# VSupply3.net
KiCad netlist of a schematic drawn in Altium Designer
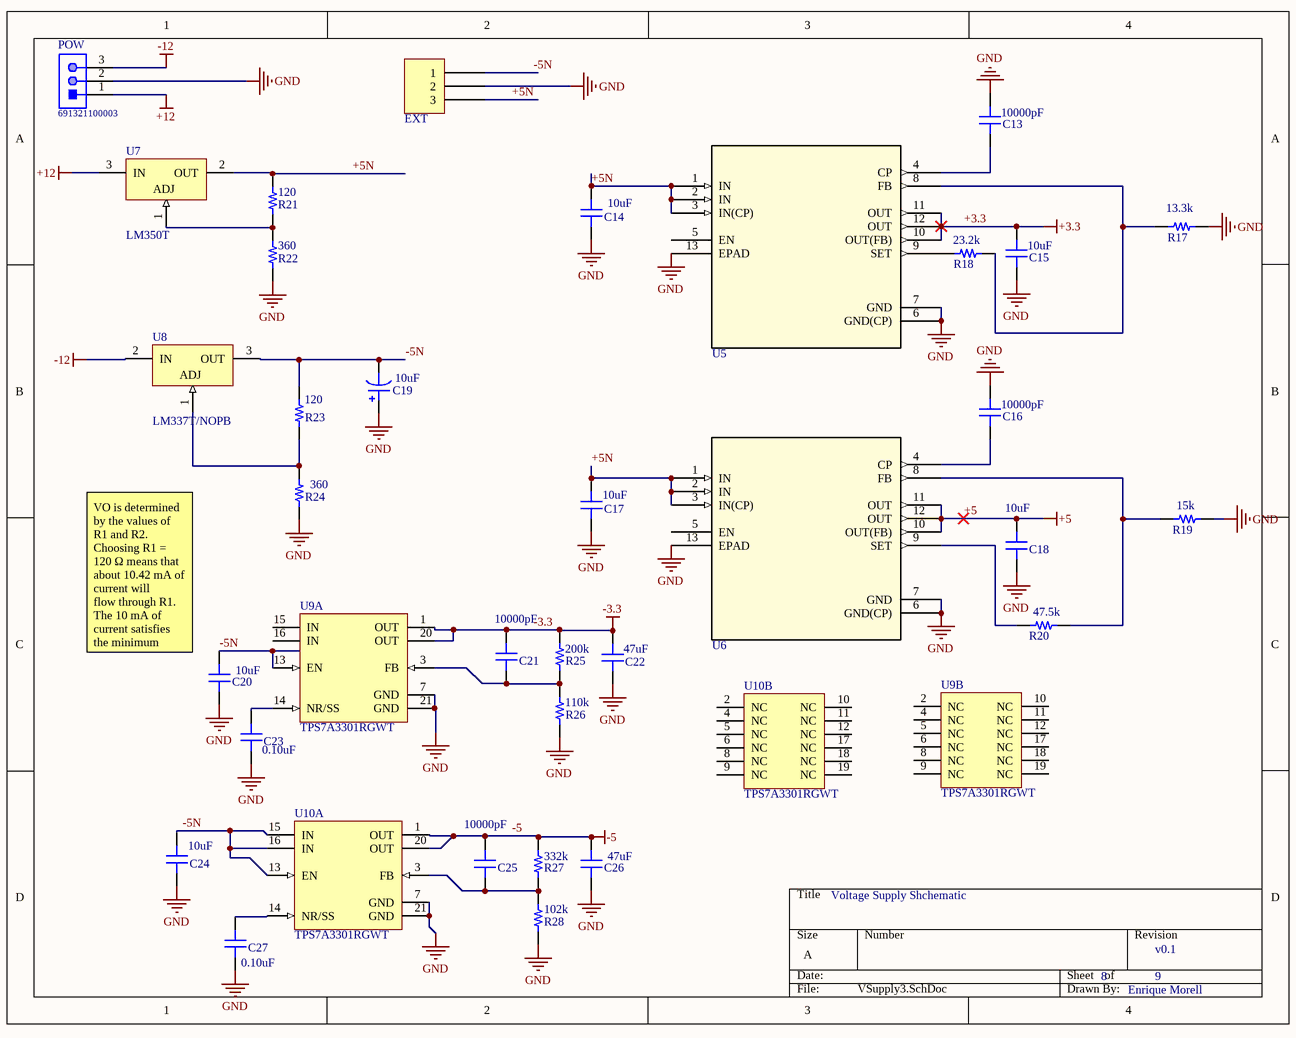
[diagram p0: VSupply3.SchDoc]

(export (version "E")
  (design (tool "Eeschema 10.0.6"))
  (components
    (comp (ref "C13")
      (value "10000pF")
      (footprint "CAP 0402/1005")
      (description "CAP CER 10000PF 16V X7R 0402")
      (fields (field (name "PART NUMBER") "C0402C103J4RACTU") (field (name "MANUFACTURER") "Kemet"))
      (libsource (lib "Celestial Library Database") (part "Capacitor"))
    )
    (comp (ref "C14")
      (value "10uF")
      (footprint "CAP 1210/3225 - 2.8MM")
      (description "CAP CER 10UF 25V X7R 1210")
      (fields
        (field (name "PART NUMBER") "CL32B106KAJNNNE")
        (field (name "MANUFACTURER") "Samsung Electro-Mechanics America, Inc.")
      )
      (libsource (lib "Celestial Library Database") (part "Capacitor"))
    )
    (comp (ref "C15")
      (value "10uF")
      (footprint "CAP 1210/3225 - 2.8MM")
      (description "CAP CER 10UF 25V X7R 1210")
      (fields
        (field (name "PART NUMBER") "CL32B106KAJNNNE")
        (field (name "MANUFACTURER") "Samsung Electro-Mechanics America, Inc.")
      )
      (libsource (lib "Celestial Library Database") (part "Capacitor"))
    )
    (comp (ref "C16")
      (value "10000pF")
      (footprint "CAP 0402/1005")
      (description "CAP CER 10000PF 16V X7R 0402")
      (fields (field (name "PART NUMBER") "C0402C103J4RACTU") (field (name "MANUFACTURER") "Kemet"))
      (libsource (lib "Celestial Library Database") (part "Capacitor"))
    )
    (comp (ref "C17")
      (value "10uF")
      (footprint "CAP 1210/3225 - 2.8MM")
      (description "CAP CER 10UF 25V X7R 1210")
      (fields
        (field (name "PART NUMBER") "CL32B106KAJNNNE")
        (field (name "MANUFACTURER") "Samsung Electro-Mechanics America, Inc.")
      )
      (libsource (lib "Celestial Library Database") (part "Capacitor"))
    )
    (comp (ref "C18")
      (value "10uF")
      (footprint "CAP 1210/3225 - 2.8MM")
      (description "CAP CER 10UF 25V X7R 1210")
      (fields
        (field (name "PART NUMBER") "CL32B106KAJNNNE")
        (field (name "MANUFACTURER") "Samsung Electro-Mechanics America, Inc.")
      )
      (libsource (lib "Celestial Library Database") (part "Capacitor"))
    )
    (comp (ref "C19")
      (value "10uF")
      (footprint "CAP POL 2917/7343")
      (description "CAP TANT 10UF 35V 20% 2917")
      (fields (field (name "PART NUMBER") "293D106X0035D2TE3") (field (name "MANUFACTURER") "Vishay Sprague"))
      (libsource (lib "Celestial Library Database") (part "Polarised Capacitor"))
    )
    (comp (ref "C20")
      (value "10uF")
      (footprint "CAP 1210/3225 - 2.8MM")
      (description "CAP CER 10UF 25V X7R 1210")
      (fields
        (field (name "PART NUMBER") "CL32B106KAJNNNE")
        (field (name "MANUFACTURER") "Samsung Electro-Mechanics America, Inc.")
      )
      (libsource (lib "Celestial Library Database") (part "Capacitor"))
    )
    (comp (ref "C21")
      (value "10000pF")
      (footprint "CAP 0402/1005")
      (description "CAP CER 10000PF 16V X7R 0402")
      (fields (field (name "PART NUMBER") "C0402C103J4RACTU") (field (name "MANUFACTURER") "Kemet"))
      (libsource (lib "Celestial Library Database") (part "Capacitor"))
    )
    (comp (ref "C22")
      (value "47uF")
      (footprint "CAP 1206/3216")
      (description "CAP CER 47UF 25V X5R 1206")
      (fields
        (field (name "PART NUMBER") "C3216X5R1E476M160AC")
        (field (name "MANUFACTURER") "TDK Corporation")
      )
      (libsource (lib "Celestial Library Database") (part "Capacitor"))
    )
    (comp (ref "C23")
      (value "0.10uF")
      (footprint "CAP 0402/1005")
      (description "CAP CER 0.1UF 16V X7R 0402")
      (fields
        (field (name "PART NUMBER") "GRM155R71C104JA88D")
        (field (name "MANUFACTURER") "Murata Electronics North America")
      )
      (libsource (lib "Celestial Library Database") (part "Capacitor"))
    )
    (comp (ref "C24")
      (value "10uF")
      (footprint "CAP 1210/3225 - 2.8MM")
      (description "CAP CER 10UF 25V X7R 1210")
      (fields
        (field (name "PART NUMBER") "CL32B106KAJNNNE")
        (field (name "MANUFACTURER") "Samsung Electro-Mechanics America, Inc.")
      )
      (libsource (lib "Celestial Library Database") (part "Capacitor"))
    )
    (comp (ref "C25")
      (value "10000pF")
      (footprint "CAP 0402/1005")
      (description "CAP CER 10000PF 16V X7R 0402")
      (fields (field (name "PART NUMBER") "C0402C103J4RACTU") (field (name "MANUFACTURER") "Kemet"))
      (libsource (lib "Celestial Library Database") (part "Capacitor"))
    )
    (comp (ref "C26")
      (value "47uF")
      (footprint "CAP 1206/3216")
      (description "CAP CER 47UF 25V X5R 1206")
      (fields
        (field (name "PART NUMBER") "C3216X5R1E476M160AC")
        (field (name "MANUFACTURER") "TDK Corporation")
      )
      (libsource (lib "Celestial Library Database") (part "Capacitor"))
    )
    (comp (ref "C27")
      (value "0.10uF")
      (footprint "CAP 0402/1005")
      (description "CAP CER 0.1UF 16V X7R 0402")
      (fields
        (field (name "PART NUMBER") "GRM155R71C104JA88D")
        (field (name "MANUFACTURER") "Murata Electronics North America")
      )
      (libsource (lib "Celestial Library Database") (part "Capacitor"))
    )
    (comp (ref "EXT")
      (value "0022272031")
      (footprint "MOLEX KK 0022272031")
      (description "CONN HEADER 3POS .100 VERT TIN")
      (fields (field (name "MANUFACTURER") "Molex, LLC"))
      (libsource (lib "Celestial Library Database") (part "3 Pin"))
    )
    (comp (ref "POW")
      (value "691321100003")
      (footprint "691321100003")
      (description "Serie 3211 - 3.50mm Vertical PCB Header WR-TBL, 3 pin")
      (fields (field (name "MANUFACTURER") "Wurth Elektronik") (field (name "PUBLISHER") "WurthElektronik"))
      (libsource (lib "Altium Content Vault") (part "WE-CN-1P-M-R3"))
    )
    (comp (ref "R17")
      (value "13.3k")
      (footprint "RES 0402/1005")
      (description "RES SMD 13.3K OHM 1% 1/10W 0402")
      (fields
        (field (name "PART NUMBER") "ERJ-2RKF1332X")
        (field (name "MANUFACTURER") "Panasonic Electronic Components")
      )
      (libsource (lib "Celestial Library Database") (part "Resistor"))
    )
    (comp (ref "R18")
      (value "23.2k")
      (footprint "RES 0402/1005")
      (description "RES SMD 23.2K OHM 1% 1/10W 0402")
      (fields
        (field (name "PART NUMBER") "ERJ-2RKF2322X")
        (field (name "MANUFACTURER") "Panasonic Electronic Components")
      )
      (libsource (lib "Celestial Library Database") (part "Resistor"))
    )
    (comp (ref "R19")
      (value "15k")
      (footprint "RES 0402/1005")
      (description "RES SMD 15K OHM 1% 1/10W 0402")
      (fields
        (field (name "PART NUMBER") "ERJ-2RKF1502X")
        (field (name "MANUFACTURER") "Panasonic Electronic Components")
      )
      (libsource (lib "Celestial Library Database") (part "Resistor"))
    )
    (comp (ref "R20")
      (value "47.5k")
      (footprint "RES 0402/1005")
      (description "RES SMD 47.5K OHM 1% 1/10W 0402")
      (fields
        (field (name "PART NUMBER") "ERJ-2RKF4752X")
        (field (name "MANUFACTURER") "Panasonic Electronic Components")
      )
      (libsource (lib "Celestial Library Database") (part "Resistor"))
    )
    (comp (ref "R21")
      (value "120")
      (footprint "RES 0402/1005")
      (description "RES SMD 120 OHM 1% 1/10W 0402")
      (fields
        (field (name "PART NUMBER") "ERJ-2RKF1200X")
        (field (name "MANUFACTURER") "Panasonic Electronic Components")
      )
      (libsource (lib "Celestial Library Database") (part "Resistor"))
    )
    (comp (ref "R22")
      (value "360")
      (footprint "RES 0402/1005")
      (description "RES SMD 360 OHM 1% 1/10W 0402")
      (fields
        (field (name "PART NUMBER") "ERJ-2RKF3600X")
        (field (name "MANUFACTURER") "Panasonic Electronic Components")
      )
      (libsource (lib "Celestial Library Database") (part "Resistor"))
    )
    (comp (ref "R23")
      (value "120")
      (footprint "RES 0402/1005")
      (description "RES SMD 120 OHM 1% 1/10W 0402")
      (fields
        (field (name "PART NUMBER") "ERJ-2RKF1200X")
        (field (name "MANUFACTURER") "Panasonic Electronic Components")
      )
      (libsource (lib "Celestial Library Database") (part "Resistor"))
    )
    (comp (ref "R24")
      (value "360")
      (footprint "RES 0402/1005")
      (description "RES SMD 360 OHM 1% 1/10W 0402")
      (fields
        (field (name "PART NUMBER") "ERJ-2RKF3600X")
        (field (name "MANUFACTURER") "Panasonic Electronic Components")
      )
      (libsource (lib "Celestial Library Database") (part "Resistor"))
    )
    (comp (ref "R25")
      (value "200k")
      (footprint "RES 0402/1005")
      (description "RES SMD 200K OHM 1% 1/10W 0402")
      (fields
        (field (name "PART NUMBER") "ERJ-2RKF2003X")
        (field (name "MANUFACTURER") "Panasonic Electronic Components")
      )
      (libsource (lib "Celestial Library Database") (part "Resistor"))
    )
    (comp (ref "R26")
      (value "110k")
      (footprint "RES 0402/1005")
      (description "RES SMD 110K OHM 1% 1/10W 0402")
      (fields
        (field (name "PART NUMBER") "ERJ-2RKF1103X")
        (field (name "MANUFACTURER") "Panasonic Electronic Components")
      )
      (libsource (lib "Celestial Library Database") (part "Resistor"))
    )
    (comp (ref "R27")
      (value "332k")
      (footprint "RES 0402/1005")
      (description "RES SMD 332K OHM 1% 1/10W 0402")
      (fields
        (field (name "PART NUMBER") "ERJ-2RKF3323X")
        (field (name "MANUFACTURER") "Panasonic Electronic Components")
      )
      (libsource (lib "Celestial Library Database") (part "Resistor"))
    )
    (comp (ref "R28")
      (value "102k")
      (footprint "RES 0402/1005")
      (description "RES SMD 102K OHM 1% 1/10W 0402")
      (fields
        (field (name "PART NUMBER") "ERJ-2RKF1023X")
        (field (name "MANUFACTURER") "Panasonic Electronic Components")
      )
      (libsource (lib "Celestial Library Database") (part "Resistor"))
    )
    (comp (ref "U5")
      (value "LP38798SDE-ADJ/NOPB")
      (footprint "TI WSON-12 DNT")
      (description "IC REG LIN POS ADJ 800MA 12WSON")
      (fields
        (field (name "MANUFACTURER") "Texas Instruments")
        (field (name "COPYRIGHT") "Copyright (C) 2018 Accelerated Designs. All rights reserved")
      )
      (libsource (lib "Celestial Library Database") (part "LP38798SDE-ADJ/N"))
    )
    (comp (ref "U6")
      (value "LP38798SDE-ADJ/NOPB")
      (footprint "TI WSON-12 DNT")
      (description "IC REG LIN POS ADJ 800MA 12WSON")
      (fields
        (field (name "MANUFACTURER") "Texas Instruments")
        (field (name "COPYRIGHT") "Copyright (C) 2018 Accelerated Designs. All rights reserved")
      )
      (libsource (lib "Celestial Library Database") (part "LP38798SDE-ADJ/N"))
    )
    (comp (ref "U7")
      (value "LM350T")
      (footprint "NDE0003A")
      (description "3-Amp Adjustable Regulator, 3-pin TO-220")
      (fields (field (name "MANUFACTURER") "Texas Instruments"))
      (libsource (lib "Altium Content Vault") (part "PM-REG-LM1086ADJ-SIL3"))
    )
    (comp (ref "U8")
      (value "LM337T/NOPB")
      (footprint "NDE0003A")
      (description "3-Terminal Adjustable Negative Regulator, 3-pin TO-220, Pb-Free")
      (fields (field (name "MANUFACTURER") "Texas Instruments"))
      (libsource (lib "Altium Content Vault") (part "PM-REG-LM150ADJ-CY3"))
    )
    (comp (ref "U9")
      (value "TPS7A3301RGWT")
      (footprint "RGW0020A_V")
      (fields (field (name "MANUFACTURER") "Texas Instruments"))
      (libsource (lib "Altium Content Vault") (part "TI-TPS7A3301RGW20"))
    )
    (comp (ref "U10")
      (value "TPS7A3301RGWT")
      (footprint "RGW0020A_V")
      (fields (field (name "MANUFACTURER") "Texas Instruments"))
      (libsource (lib "Altium Content Vault") (part "TI-TPS7A3301RGW20"))
    )
  )
  (nets
    (net (code "1") (name "+3.3") (class "Default")
      (node (ref "C15") (pin "2") (pinfunction "2_2") (pintype "passive"))
      (node (ref "U5") (pin "10") (pinfunction "OUT(FB)_10") (pintype "output"))
      (node (ref "U5") (pin "11") (pinfunction "OUT_11") (pintype "output"))
      (node (ref "U5") (pin "12") (pinfunction "OUT_12") (pintype "output"))
    )
    (net (code "2") (name "+5") (class "Default")
      (node (ref "C18") (pin "2") (pinfunction "2_2") (pintype "passive"))
      (node (ref "U6") (pin "10") (pinfunction "OUT(FB)_10") (pintype "output"))
      (node (ref "U6") (pin "11") (pinfunction "OUT_11") (pintype "output"))
      (node (ref "U6") (pin "12") (pinfunction "OUT_12") (pintype "output"))
    )
    (net (code "3") (name "+12") (class "Default")
      (node (ref "POW") (pin "1") (pinfunction "1_1") (pintype "passive"))
      (node (ref "U7") (pin "3") (pinfunction "IN_3") (pintype "power_in"))
    )
    (net (code "4") (name "-3.3") (class "Default")
      (node (ref "C21") (pin "1") (pinfunction "1_1") (pintype "passive"))
      (node (ref "C22") (pin "2") (pinfunction "2_2") (pintype "passive"))
      (node (ref "R25") (pin "2") (pinfunction "2_2") (pintype "passive"))
      (node (ref "U9") (pin "1") (pinfunction "OUT_1") (pintype "power_in"))
      (node (ref "U9") (pin "20") (pinfunction "OUT_20") (pintype "power_in"))
    )
    (net (code "5") (name "-5") (class "Default")
      (node (ref "C25") (pin "1") (pinfunction "1_1") (pintype "passive"))
      (node (ref "C26") (pin "2") (pinfunction "2_2") (pintype "passive"))
      (node (ref "R27") (pin "2") (pinfunction "2_2") (pintype "passive"))
      (node (ref "U10") (pin "1") (pinfunction "OUT_1") (pintype "power_in"))
      (node (ref "U10") (pin "20") (pinfunction "OUT_20") (pintype "power_in"))
    )
    (net (code "6") (name "-12") (class "Default")
      (node (ref "POW") (pin "3") (pinfunction "3_3") (pintype "passive"))
      (node (ref "U8") (pin "2") (pinfunction "IN_2") (pintype "power_in"))
    )
    (net (code "7") (name "/+5N") (class "Default")
      (node (ref "C14") (pin "2") (pinfunction "2_2") (pintype "passive"))
      (node (ref "C17") (pin "2") (pinfunction "2_2") (pintype "passive"))
      (node (ref "EXT") (pin "3") (pinfunction "3_3") (pintype "passive"))
      (node (ref "R21") (pin "2") (pinfunction "2_2") (pintype "passive"))
      (node (ref "U5") (pin "1") (pinfunction "IN_1") (pintype "input"))
      (node (ref "U5") (pin "2") (pinfunction "IN_2") (pintype "input"))
      (node (ref "U5") (pin "3") (pinfunction "IN(CP)_3") (pintype "input"))
      (node (ref "U6") (pin "1") (pinfunction "IN_1") (pintype "input"))
      (node (ref "U6") (pin "2") (pinfunction "IN_2") (pintype "input"))
      (node (ref "U6") (pin "3") (pinfunction "IN(CP)_3") (pintype "input"))
      (node (ref "U7") (pin "2") (pinfunction "OUT_2") (pintype "power_in"))
    )
    (net (code "8") (name "/-5N") (class "Default")
      (node (ref "C19") (pin "2") (pinfunction "2_2") (pintype "passive"))
      (node (ref "C20") (pin "2") (pinfunction "2_2") (pintype "passive"))
      (node (ref "C24") (pin "2") (pinfunction "2_2") (pintype "passive"))
      (node (ref "EXT") (pin "1") (pinfunction "1_1") (pintype "passive"))
      (node (ref "R23") (pin "2") (pinfunction "2_2") (pintype "passive"))
      (node (ref "U10") (pin "13") (pinfunction "EN_13") (pintype "input"))
      (node (ref "U10") (pin "15") (pinfunction "IN_15") (pintype "power_in"))
      (node (ref "U10") (pin "16") (pinfunction "IN_16") (pintype "power_in"))
      (node (ref "U8") (pin "3") (pinfunction "OUT_3") (pintype "power_in"))
      (node (ref "U9") (pin "13") (pinfunction "EN_13") (pintype "input"))
    )
    (net (code "9") (name "GND") (class "Default")
      (node (ref "C13") (pin "2") (pinfunction "2_2") (pintype "passive"))
      (node (ref "C14") (pin "1") (pinfunction "1_1") (pintype "passive"))
      (node (ref "C15") (pin "1") (pinfunction "1_1") (pintype "passive"))
      (node (ref "C16") (pin "2") (pinfunction "2_2") (pintype "passive"))
      (node (ref "C17") (pin "1") (pinfunction "1_1") (pintype "passive"))
      (node (ref "C18") (pin "1") (pinfunction "1_1") (pintype "passive"))
      (node (ref "C19") (pin "1") (pinfunction "1_1") (pintype "passive"))
      (node (ref "C20") (pin "1") (pinfunction "1_1") (pintype "passive"))
      (node (ref "C22") (pin "1") (pinfunction "1_1") (pintype "passive"))
      (node (ref "C23") (pin "1") (pinfunction "1_1") (pintype "passive"))
      (node (ref "C24") (pin "1") (pinfunction "1_1") (pintype "passive"))
      (node (ref "C26") (pin "1") (pinfunction "1_1") (pintype "passive"))
      (node (ref "C27") (pin "1") (pinfunction "1_1") (pintype "passive"))
      (node (ref "EXT") (pin "2") (pinfunction "2_2") (pintype "passive"))
      (node (ref "POW") (pin "2") (pinfunction "2_2") (pintype "passive"))
      (node (ref "R17") (pin "2") (pinfunction "2_2") (pintype "passive"))
      (node (ref "R19") (pin "2") (pinfunction "2_2") (pintype "passive"))
      (node (ref "R22") (pin "1") (pinfunction "1_1") (pintype "passive"))
      (node (ref "R24") (pin "1") (pinfunction "1_1") (pintype "passive"))
      (node (ref "R26") (pin "1") (pinfunction "1_1") (pintype "passive"))
      (node (ref "R28") (pin "1") (pinfunction "1_1") (pintype "passive"))
      (node (ref "U10") (pin "21") (pinfunction "GND_21") (pintype "power_in"))
      (node (ref "U10") (pin "7") (pinfunction "GND_7") (pintype "power_in"))
      (node (ref "U5") (pin "13") (pinfunction "EPAD_13") (pintype "passive"))
      (node (ref "U5") (pin "6") (pinfunction "GND(CP)_6") (pintype "power_in"))
      (node (ref "U5") (pin "7") (pinfunction "GND_7") (pintype "power_in"))
      (node (ref "U6") (pin "13") (pinfunction "EPAD_13") (pintype "passive"))
      (node (ref "U6") (pin "6") (pinfunction "GND(CP)_6") (pintype "power_in"))
      (node (ref "U6") (pin "7") (pinfunction "GND_7") (pintype "power_in"))
      (node (ref "U9") (pin "21") (pinfunction "GND_21") (pintype "power_in"))
      (node (ref "U9") (pin "7") (pinfunction "GND_7") (pintype "power_in"))
    )
    (net (code "10") (name "Net-(U5-CP)") (class "Default")
      (node (ref "C13") (pin "1") (pinfunction "1_1") (pintype "passive"))
      (node (ref "U5") (pin "4") (pinfunction "CP_4") (pintype "output"))
    )
    (net (code "11") (name "Net-(U5-FB)") (class "Default")
      (node (ref "R17") (pin "1") (pinfunction "1_1") (pintype "passive"))
      (node (ref "R18") (pin "2") (pinfunction "2_2") (pintype "passive"))
      (node (ref "U5") (pin "8") (pinfunction "FB_8") (pintype "output"))
    )
    (net (code "12") (name "Net-(U5-SET)") (class "Default")
      (node (ref "R18") (pin "1") (pinfunction "1_1") (pintype "passive"))
      (node (ref "U5") (pin "9") (pinfunction "SET_9") (pintype "output"))
    )
    (net (code "13") (name "Net-(U6-CP)") (class "Default")
      (node (ref "C16") (pin "1") (pinfunction "1_1") (pintype "passive"))
      (node (ref "U6") (pin "4") (pinfunction "CP_4") (pintype "output"))
    )
    (net (code "14") (name "Net-(U6-FB)") (class "Default")
      (node (ref "R19") (pin "1") (pinfunction "1_1") (pintype "passive"))
      (node (ref "R20") (pin "2") (pinfunction "2_2") (pintype "passive"))
      (node (ref "U6") (pin "8") (pinfunction "FB_8") (pintype "output"))
    )
    (net (code "15") (name "Net-(U6-SET)") (class "Default")
      (node (ref "R20") (pin "1") (pinfunction "1_1") (pintype "passive"))
      (node (ref "U6") (pin "9") (pinfunction "SET_9") (pintype "output"))
    )
    (net (code "16") (name "Net-(U7-ADJ)") (class "Default")
      (node (ref "R21") (pin "1") (pinfunction "1_1") (pintype "passive"))
      (node (ref "R22") (pin "2") (pinfunction "2_2") (pintype "passive"))
      (node (ref "U7") (pin "1") (pinfunction "ADJ_1") (pintype "input"))
    )
    (net (code "17") (name "Net-(U8-ADJ)") (class "Default")
      (node (ref "R23") (pin "1") (pinfunction "1_1") (pintype "passive"))
      (node (ref "R24") (pin "2") (pinfunction "2_2") (pintype "passive"))
      (node (ref "U8") (pin "1") (pinfunction "ADJ_1") (pintype "input"))
    )
    (net (code "18") (name "Net-(U9A-FB)") (class "Default")
      (node (ref "C21") (pin "2") (pinfunction "2_2") (pintype "passive"))
      (node (ref "R25") (pin "1") (pinfunction "1_1") (pintype "passive"))
      (node (ref "R26") (pin "2") (pinfunction "2_2") (pintype "passive"))
      (node (ref "U9") (pin "3") (pinfunction "FB_3") (pintype "input"))
    )
    (net (code "19") (name "Net-(U9A-NR{slash}SS)") (class "Default")
      (node (ref "C23") (pin "2") (pinfunction "2_2") (pintype "passive"))
      (node (ref "U9") (pin "14") (pinfunction "NR/SS_14") (pintype "input"))
    )
    (net (code "20") (name "Net-(U10A-FB)") (class "Default")
      (node (ref "C25") (pin "2") (pinfunction "2_2") (pintype "passive"))
      (node (ref "R27") (pin "1") (pinfunction "1_1") (pintype "passive"))
      (node (ref "R28") (pin "2") (pinfunction "2_2") (pintype "passive"))
      (node (ref "U10") (pin "3") (pinfunction "FB_3") (pintype "input"))
    )
    (net (code "21") (name "Net-(U10A-NR{slash}SS)") (class "Default")
      (node (ref "C27") (pin "2") (pinfunction "2_2") (pintype "passive"))
      (node (ref "U10") (pin "14") (pinfunction "NR/SS_14") (pintype "input"))
    )
    (net (code "22") (name "unconnected-(U5-EN-Pad5)") (class "Default")
      (node (ref "U5") (pin "5") (pinfunction "EN_5") (pintype "passive"))
    )
    (net (code "23") (name "unconnected-(U6-EN-Pad5)") (class "Default")
      (node (ref "U6") (pin "5") (pinfunction "EN_5") (pintype "passive"))
    )
    (net (code "24") (name "unconnected-(U9A-IN-Pad15)") (class "Default")
      (node (ref "U9") (pin "15") (pinfunction "IN_15") (pintype "power_in"))
    )
    (net (code "25") (name "unconnected-(U9A-IN-Pad16)") (class "Default")
      (node (ref "U9") (pin "16") (pinfunction "IN_16") (pintype "power_in"))
    )
    (net (code "26") (name "unconnected-(U9B-NC-Pad2)") (class "Default")
      (node (ref "U9") (pin "2") (pinfunction "NC_2") (pintype "passive"))
    )
    (net (code "27") (name "unconnected-(U9B-NC-Pad4)") (class "Default")
      (node (ref "U9") (pin "4") (pinfunction "NC_4") (pintype "passive"))
    )
    (net (code "28") (name "unconnected-(U9B-NC-Pad5)") (class "Default")
      (node (ref "U9") (pin "5") (pinfunction "NC_5") (pintype "passive"))
    )
    (net (code "29") (name "unconnected-(U9B-NC-Pad6)") (class "Default")
      (node (ref "U9") (pin "6") (pinfunction "NC_6") (pintype "passive"))
    )
    (net (code "30") (name "unconnected-(U9B-NC-Pad8)") (class "Default")
      (node (ref "U9") (pin "8") (pinfunction "NC_8") (pintype "passive"))
    )
    (net (code "31") (name "unconnected-(U9B-NC-Pad9)") (class "Default")
      (node (ref "U9") (pin "9") (pinfunction "NC_9") (pintype "passive"))
    )
    (net (code "32") (name "unconnected-(U9B-NC-Pad10)") (class "Default")
      (node (ref "U9") (pin "10") (pinfunction "NC_10") (pintype "passive"))
    )
    (net (code "33") (name "unconnected-(U9B-NC-Pad11)") (class "Default")
      (node (ref "U9") (pin "11") (pinfunction "NC_11") (pintype "passive"))
    )
    (net (code "34") (name "unconnected-(U9B-NC-Pad12)") (class "Default")
      (node (ref "U9") (pin "12") (pinfunction "NC_12") (pintype "passive"))
    )
    (net (code "35") (name "unconnected-(U9B-NC-Pad17)") (class "Default")
      (node (ref "U9") (pin "17") (pinfunction "NC_17") (pintype "passive"))
    )
    (net (code "36") (name "unconnected-(U9B-NC-Pad18)") (class "Default")
      (node (ref "U9") (pin "18") (pinfunction "NC_18") (pintype "passive"))
    )
    (net (code "37") (name "unconnected-(U9B-NC-Pad19)") (class "Default")
      (node (ref "U9") (pin "19") (pinfunction "NC_19") (pintype "passive"))
    )
    (net (code "38") (name "unconnected-(U10B-NC-Pad2)") (class "Default")
      (node (ref "U10") (pin "2") (pinfunction "NC_2") (pintype "passive"))
    )
    (net (code "39") (name "unconnected-(U10B-NC-Pad4)") (class "Default")
      (node (ref "U10") (pin "4") (pinfunction "NC_4") (pintype "passive"))
    )
    (net (code "40") (name "unconnected-(U10B-NC-Pad5)") (class "Default")
      (node (ref "U10") (pin "5") (pinfunction "NC_5") (pintype "passive"))
    )
    (net (code "41") (name "unconnected-(U10B-NC-Pad6)") (class "Default")
      (node (ref "U10") (pin "6") (pinfunction "NC_6") (pintype "passive"))
    )
    (net (code "42") (name "unconnected-(U10B-NC-Pad8)") (class "Default")
      (node (ref "U10") (pin "8") (pinfunction "NC_8") (pintype "passive"))
    )
    (net (code "43") (name "unconnected-(U10B-NC-Pad9)") (class "Default")
      (node (ref "U10") (pin "9") (pinfunction "NC_9") (pintype "passive"))
    )
    (net (code "44") (name "unconnected-(U10B-NC-Pad10)") (class "Default")
      (node (ref "U10") (pin "10") (pinfunction "NC_10") (pintype "passive"))
    )
    (net (code "45") (name "unconnected-(U10B-NC-Pad11)") (class "Default")
      (node (ref "U10") (pin "11") (pinfunction "NC_11") (pintype "passive"))
    )
    (net (code "46") (name "unconnected-(U10B-NC-Pad12)") (class "Default")
      (node (ref "U10") (pin "12") (pinfunction "NC_12") (pintype "passive"))
    )
    (net (code "47") (name "unconnected-(U10B-NC-Pad17)") (class "Default")
      (node (ref "U10") (pin "17") (pinfunction "NC_17") (pintype "passive"))
    )
    (net (code "48") (name "unconnected-(U10B-NC-Pad18)") (class "Default")
      (node (ref "U10") (pin "18") (pinfunction "NC_18") (pintype "passive"))
    )
    (net (code "49") (name "unconnected-(U10B-NC-Pad19)") (class "Default")
      (node (ref "U10") (pin "19") (pinfunction "NC_19") (pintype "passive"))
    )
  )
)
